# explore.net
KiCad netlist of a schematic drawn in EAGLE
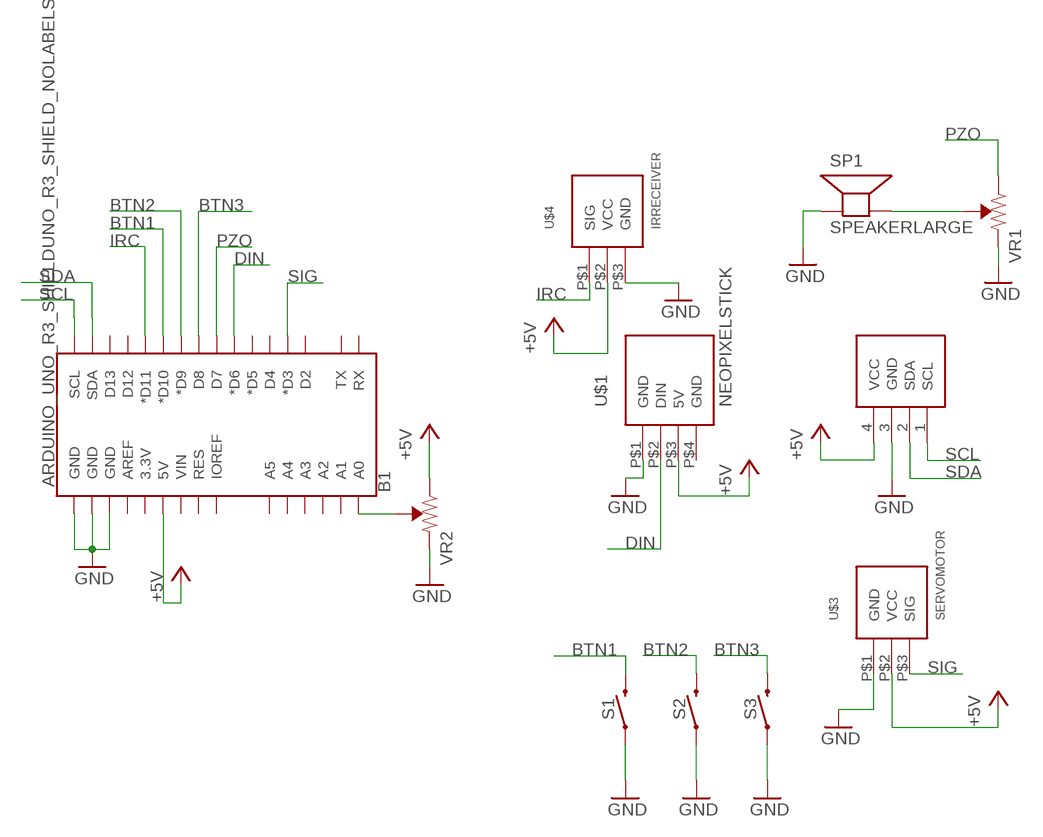
[diagram p0: schematic, sheet 1]

(export (version "E")
  (design (tool "Eeschema 10.0.6"))
  (components
    (comp (ref "B1")
      (value "ARDUINO_UNO_R3_SHIELDUNO_R3_SHIELD_NOLABELS_LOCK")
      (footprint "eagle-import:UNO_R3_SHIELD_NOLABELS_LOCK")
      (libsource (lib "eagle-import") (part "ARDUINO_UNO_R3_SHIELDUNO_R3_SHIELD_NOLABELS_LOCK"))
    )
    (comp (ref "S1")
      (value "MOMENTARY-SWITCH-SPST-PTH-6.0MM")
      (footprint "eagle-import:TACTILE_SWITCH_PTH_6.0MM")
      (libsource (lib "eagle-import") (part "MOMENTARY-SWITCH-SPST-PTH-6.0MM"))
    )
    (comp (ref "S2")
      (value "MOMENTARY-SWITCH-SPST-PTH-6.0MM")
      (footprint "eagle-import:TACTILE_SWITCH_PTH_6.0MM")
      (libsource (lib "eagle-import") (part "MOMENTARY-SWITCH-SPST-PTH-6.0MM"))
    )
    (comp (ref "S3")
      (value "MOMENTARY-SWITCH-SPST-PTH-6.0MM")
      (footprint "eagle-import:TACTILE_SWITCH_PTH_6.0MM")
      (libsource (lib "eagle-import") (part "MOMENTARY-SWITCH-SPST-PTH-6.0MM"))
    )
    (comp (ref "SP1")
      (value "SPEAKERLARGE")
      (footprint "eagle-import:2-HOLE_LARGE")
      (libsource (lib "eagle-import") (part "SPEAKERLARGE"))
    )
    (comp (ref "U$1")
      (value "NEOPIXELSTICK")
      (footprint "eagle-import:NEOPIXELSTICK")
      (libsource (lib "eagle-import") (part "NEOPIXELSTICK"))
    )
    (comp (ref "U$2")
      (value "4DIGITDISPLAYOUTLINE")
      (footprint "eagle-import:4DIGITDISPLAY")
      (libsource (lib "eagle-import") (part "4DIGITDISPLAYOUTLINE"))
    )
    (comp (ref "U$3")
      (value "SERVOMOTOR")
      (footprint "eagle-import:3-HOLE-LARGE")
      (libsource (lib "eagle-import") (part "SERVOMOTOR"))
    )
    (comp (ref "U$4")
      (value "IRRECEIVER")
      (footprint "eagle-import:3-HOLE-LARGE")
      (libsource (lib "eagle-import") (part "IRRECEIVER"))
    )
    (comp (ref "VR1")
      (value "TRIMPOTSTANDARD")
      (footprint "eagle-import:POTENTIOMETER")
      (libsource (lib "eagle-import") (part "TRIMPOTSTANDARD"))
    )
    (comp (ref "VR2")
      (value "TRIMPOTSTANDARD")
      (footprint "eagle-import:POTENTIOMETER")
      (libsource (lib "eagle-import") (part "TRIMPOTSTANDARD"))
    )
  )
  (nets
    (net (code "1") (name "+5V") (class "Default")
      (node (ref "B1") (pin "5V") (pinfunction "5V_5V") (pintype "bidirectional"))
      (node (ref "U$1") (pin "P$3") (pinfunction "5V_P$3") (pintype "bidirectional"))
      (node (ref "U$2") (pin "4") (pinfunction "VCC_4") (pintype "bidirectional"))
      (node (ref "U$3") (pin "P$2") (pinfunction "VCC_P$2") (pintype "bidirectional"))
      (node (ref "U$4") (pin "P$2") (pinfunction "VCC_P$2") (pintype "bidirectional"))
      (node (ref "VR2") (pin "P$3") (pinfunction "CW_P$3") (pintype "passive"))
    )
    (net (code "2") (name "/BTN1") (class "Default")
      (node (ref "B1") (pin "D10") (pinfunction "*D10_D10") (pintype "bidirectional"))
      (node (ref "S1") (pin "3") (pinfunction "2_3") (pintype "passive"))
    )
    (net (code "3") (name "/BTN2") (class "Default")
      (node (ref "B1") (pin "D9") (pinfunction "*D9_D9") (pintype "bidirectional"))
      (node (ref "S2") (pin "3") (pinfunction "2_3") (pintype "passive"))
    )
    (net (code "4") (name "/BTN3") (class "Default")
      (node (ref "B1") (pin "D8") (pinfunction "D8_D8") (pintype "bidirectional"))
      (node (ref "S3") (pin "3") (pinfunction "2_3") (pintype "passive"))
    )
    (net (code "5") (name "/DIN") (class "Default")
      (node (ref "B1") (pin "D6") (pinfunction "*D6_D6") (pintype "bidirectional"))
      (node (ref "U$1") (pin "P$2") (pinfunction "DIN_P$2") (pintype "bidirectional"))
    )
    (net (code "6") (name "/IRC") (class "Default")
      (node (ref "B1") (pin "D11") (pinfunction "*D11_D11") (pintype "bidirectional"))
      (node (ref "U$4") (pin "P$1") (pinfunction "SIG_P$1") (pintype "bidirectional"))
    )
    (net (code "7") (name "/PZO") (class "Default")
      (node (ref "B1") (pin "D7") (pinfunction "D7_D7") (pintype "bidirectional"))
      (node (ref "VR1") (pin "P$3") (pinfunction "CW_P$3") (pintype "passive"))
    )
    (net (code "8") (name "/SCL") (class "Default")
      (node (ref "B1") (pin "SCL") (pinfunction "SCL_SCL") (pintype "bidirectional"))
      (node (ref "U$2") (pin "1") (pinfunction "SCL_1") (pintype "bidirectional"))
    )
    (net (code "9") (name "/SDA") (class "Default")
      (node (ref "B1") (pin "SDA") (pinfunction "SDA_SDA") (pintype "bidirectional"))
      (node (ref "U$2") (pin "2") (pinfunction "SDA_2") (pintype "bidirectional"))
    )
    (net (code "10") (name "/SIG") (class "Default")
      (node (ref "B1") (pin "D3") (pinfunction "*D3_D3") (pintype "bidirectional"))
      (node (ref "U$3") (pin "P$3") (pinfunction "SIG_P$3") (pintype "bidirectional"))
    )
    (net (code "11") (name "GND") (class "Default")
      (node (ref "B1") (pin "GND@0") (pinfunction "GND_GND@0") (pintype "bidirectional"))
      (node (ref "B1") (pin "GND@1") (pinfunction "GND_GND@1") (pintype "bidirectional"))
      (node (ref "B1") (pin "GND@2") (pinfunction "GND_GND@2") (pintype "bidirectional"))
      (node (ref "S1") (pin "1") (pinfunction "1_1") (pintype "passive"))
      (node (ref "S2") (pin "1") (pinfunction "1_1") (pintype "passive"))
      (node (ref "S3") (pin "1") (pinfunction "1_1") (pintype "passive"))
      (node (ref "SP1") (pin "P$1") (pinfunction "+_P$1") (pintype "passive"))
      (node (ref "U$1") (pin "P$1") (pinfunction "GND_P$1") (pintype "bidirectional"))
      (node (ref "U$2") (pin "3") (pinfunction "GND_3") (pintype "bidirectional"))
      (node (ref "U$3") (pin "P$1") (pinfunction "GND_P$1") (pintype "bidirectional"))
      (node (ref "U$4") (pin "P$3") (pinfunction "GND_P$3") (pintype "bidirectional"))
      (node (ref "VR1") (pin "P$1") (pinfunction "CCW_P$1") (pintype "passive"))
      (node (ref "VR2") (pin "P$1") (pinfunction "CCW_P$1") (pintype "passive"))
    )
    (net (code "12") (name "Net-(SP1--)") (class "Default")
      (node (ref "SP1") (pin "P$2") (pinfunction "-_P$2") (pintype "passive"))
      (node (ref "VR1") (pin "P$2") (pinfunction "WIPER_P$2") (pintype "passive"))
    )
    (net (code "13") (name "Net-(VR2-WIPER)") (class "Default")
      (node (ref "B1") (pin "A0") (pinfunction "A0_A0") (pintype "bidirectional"))
      (node (ref "VR2") (pin "P$2") (pinfunction "WIPER_P$2") (pintype "passive"))
    )
    (net (code "14") (name "unconnected-(B1-*D5-PadD5)") (class "Default")
      (node (ref "B1") (pin "D5") (pinfunction "*D5_D5") (pintype "bidirectional"))
    )
    (net (code "15") (name "unconnected-(B1-Pad3.3V)") (class "Default")
      (node (ref "B1") (pin "3.3V") (pinfunction "3.3V_3.3V") (pintype "bidirectional"))
    )
    (net (code "16") (name "unconnected-(B1-PadA1)") (class "Default")
      (node (ref "B1") (pin "A1") (pinfunction "A1_A1") (pintype "bidirectional"))
    )
    (net (code "17") (name "unconnected-(B1-PadA2)") (class "Default")
      (node (ref "B1") (pin "A2") (pinfunction "A2_A2") (pintype "bidirectional"))
    )
    (net (code "18") (name "unconnected-(B1-PadA3)") (class "Default")
      (node (ref "B1") (pin "A3") (pinfunction "A3_A3") (pintype "bidirectional"))
    )
    (net (code "19") (name "unconnected-(B1-PadA4)") (class "Default")
      (node (ref "B1") (pin "A4") (pinfunction "A4_A4") (pintype "bidirectional"))
    )
    (net (code "20") (name "unconnected-(B1-PadA5)") (class "Default")
      (node (ref "B1") (pin "A5") (pinfunction "A5_A5") (pintype "bidirectional"))
    )
    (net (code "21") (name "unconnected-(B1-PadAREF)") (class "Default")
      (node (ref "B1") (pin "AREF") (pinfunction "AREF_AREF") (pintype "bidirectional"))
    )
    (net (code "22") (name "unconnected-(B1-PadD2)") (class "Default")
      (node (ref "B1") (pin "D2") (pinfunction "D2_D2") (pintype "bidirectional"))
    )
    (net (code "23") (name "unconnected-(B1-PadD4)") (class "Default")
      (node (ref "B1") (pin "D4") (pinfunction "D4_D4") (pintype "bidirectional"))
    )
    (net (code "24") (name "unconnected-(B1-PadD12)") (class "Default")
      (node (ref "B1") (pin "D12") (pinfunction "D12_D12") (pintype "bidirectional"))
    )
    (net (code "25") (name "unconnected-(B1-PadD13)") (class "Default")
      (node (ref "B1") (pin "D13") (pinfunction "D13_D13") (pintype "bidirectional"))
    )
    (net (code "26") (name "unconnected-(B1-PadIOREF)") (class "Default")
      (node (ref "B1") (pin "IOREF") (pinfunction "IOREF_IOREF") (pintype "bidirectional"))
    )
    (net (code "27") (name "unconnected-(B1-PadRES)") (class "Default")
      (node (ref "B1") (pin "RES") (pinfunction "RES_RES") (pintype "bidirectional"))
    )
    (net (code "28") (name "unconnected-(B1-PadRX)") (class "Default")
      (node (ref "B1") (pin "RX") (pinfunction "RX_RX") (pintype "bidirectional"))
    )
    (net (code "29") (name "unconnected-(B1-PadTX)") (class "Default")
      (node (ref "B1") (pin "TX") (pinfunction "TX_TX") (pintype "bidirectional"))
    )
    (net (code "30") (name "unconnected-(B1-PadVIN)") (class "Default")
      (node (ref "B1") (pin "VIN") (pinfunction "VIN_VIN") (pintype "bidirectional"))
    )
    (net (code "31") (name "unconnected-(U$1-GND-PadP$4)") (class "Default")
      (node (ref "U$1") (pin "P$4") (pinfunction "GND_P$4") (pintype "bidirectional"))
    )
  )
)
